# MODULIQ_UART.net
KiCad netlist of a schematic drawn in Altium Designer
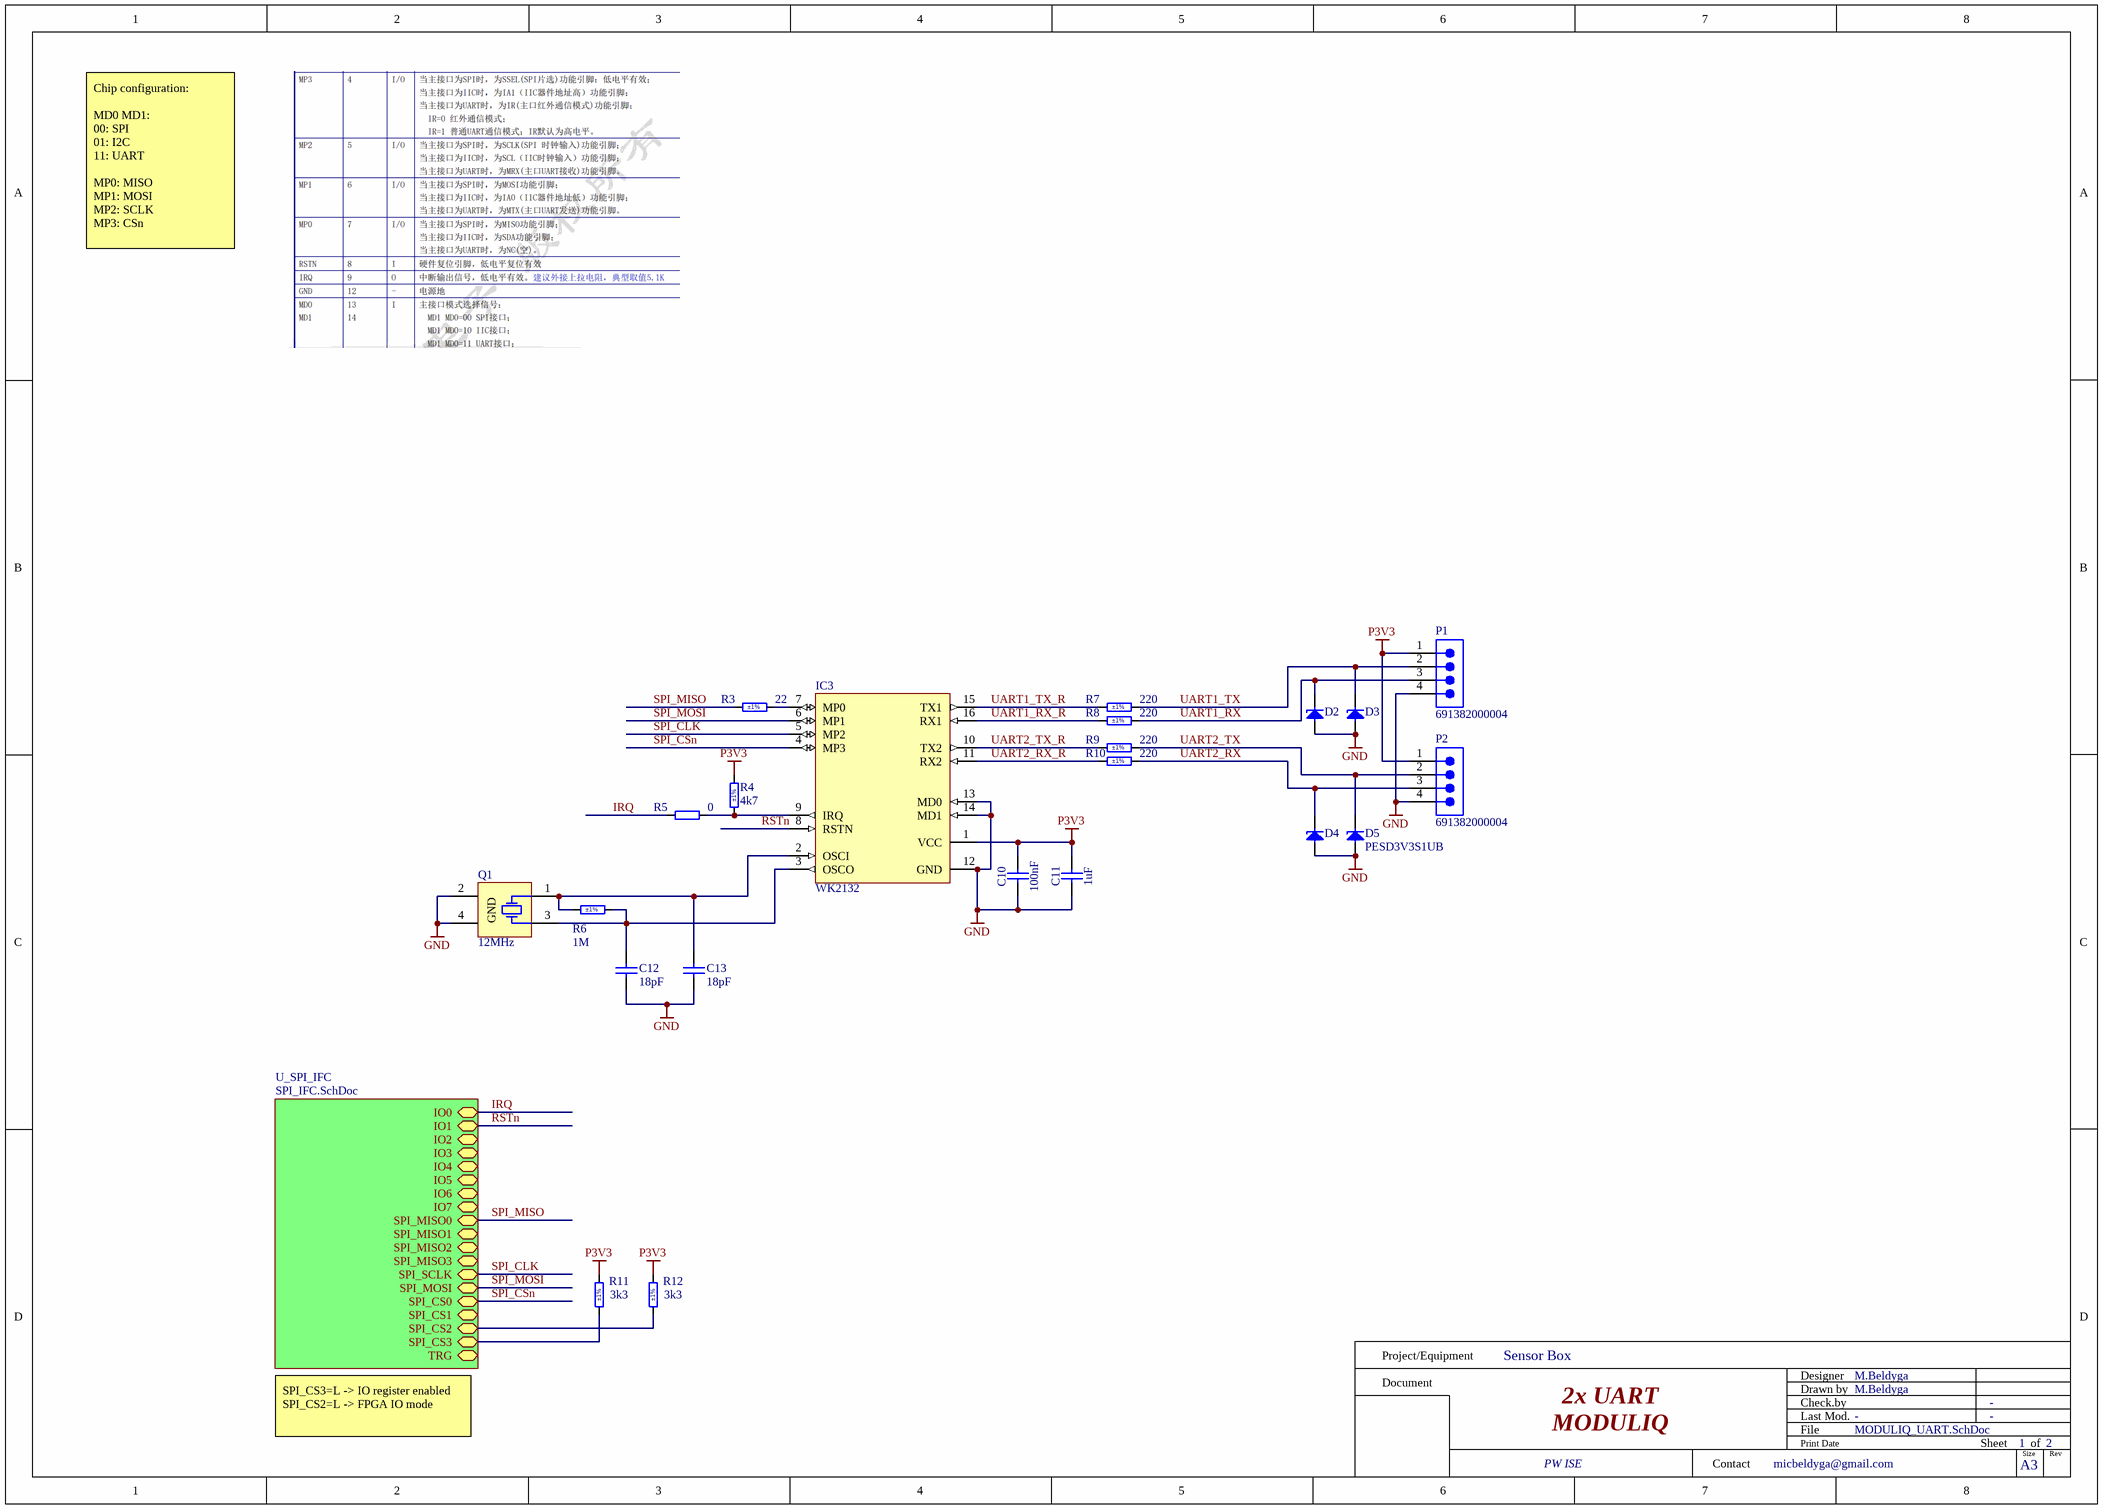
[diagram p0: MODULIQ_UART.SchDoc]

(export (version "E")
  (design (tool "Eeschema 10.0.6"))
  (components
    (comp (ref "C10")
      (value "100nF")
      (footprint "CAPC1005X55N")
      (description "Non-polarised capacitor")
      (fields
        (field (name "PART NUMBER") "CC0402_100NF_16V_10%_X7R")
        (field (name "VOLTAGE") "16V")
        (field (name "AUTHOR") "CERN DEM JLC")
      )
      (libsource (lib "Capacitors") (part "Capacitor - non polarized"))
    )
    (comp (ref "C11")
      (value "1uF")
      (footprint "CAPC1005X55N")
      (description "Non-polarised capacitor")
      (fields
        (field (name "PART NUMBER") "CC0402_1UF_16V_10%_X5R")
        (field (name "VOLTAGE") "16V")
        (field (name "AUTHOR") "CERN DEM JLC")
      )
      (libsource (lib "Capacitors") (part "Capacitor - non polarized"))
    )
    (comp (ref "C12")
      (value "18pF")
      (footprint "CAPC1005X55N")
      (description "Non-polarised capacitor")
      (fields
        (field (name "PART NUMBER") "CC0402_18PF_50V_5%_C0G")
        (field (name "VOLTAGE") "50V")
        (field (name "AUTHOR") "CERN DEM JLC")
      )
      (libsource (lib "Capacitors") (part "Capacitor - non polarized"))
    )
    (comp (ref "C13")
      (value "18pF")
      (footprint "CAPC1005X55N")
      (description "Non-polarised capacitor")
      (fields
        (field (name "PART NUMBER") "CC0402_18PF_50V_5%_C0G")
        (field (name "VOLTAGE") "50V")
        (field (name "AUTHOR") "CERN DEM JLC")
      )
      (libsource (lib "Capacitors") (part "Capacitor - non polarized"))
    )
    (comp (ref "D2")
      (value "PESD3V3S1UB")
      (footprint "SODFL1608X65N")
      (description "ESD protection diode")
      (fields
        (field (name "VOLTAGE") "3V3")
        (field (name "POWER") "330W")
        (field (name "AUTHOR") "CERN DEM JLC")
      )
      (libsource (lib "ICs And Semiconductors") (part "Diode ESD"))
    )
    (comp (ref "D3")
      (value "PESD3V3S1UB")
      (footprint "SODFL1608X65N")
      (description "ESD protection diode")
      (fields
        (field (name "VOLTAGE") "3V3")
        (field (name "POWER") "330W")
        (field (name "AUTHOR") "CERN DEM JLC")
      )
      (libsource (lib "ICs And Semiconductors") (part "Diode ESD"))
    )
    (comp (ref "D4")
      (value "PESD3V3S1UB")
      (footprint "SODFL1608X65N")
      (description "ESD protection diode")
      (fields
        (field (name "VOLTAGE") "3V3")
        (field (name "POWER") "330W")
        (field (name "AUTHOR") "CERN DEM JLC")
      )
      (libsource (lib "ICs And Semiconductors") (part "Diode ESD"))
    )
    (comp (ref "D5")
      (value "PESD3V3S1UB")
      (footprint "SODFL1608X65N")
      (description "ESD protection diode")
      (fields
        (field (name "VOLTAGE") "3V3")
        (field (name "POWER") "330W")
        (field (name "AUTHOR") "CERN DEM JLC")
      )
      (libsource (lib "ICs And Semiconductors") (part "Diode ESD"))
    )
    (comp (ref "IC3")
      (value "WK2132")
      (footprint "SOP65P780X195-16N")
      (description "2 Channel SPI-to-UART converter")
      (fields (field (name "MANUFACTURER PART NUMBER") "WK2132-ISSG") (field (name "MANUFACTURER") "Weikai"))
      (libsource (lib "mb") (part "WK2132"))
    )
    (comp (ref "P1")
      (value "691382000004")
      (footprint "691382000004")
      (description "WR-TBL Series 382 Vertical PCB Header, THT, pitch 2.5mm, 4p")
      (fields (field (name "MANUFACTURER") "Wurth Elektronik"))
      (libsource (lib "WE - Electromechanical Components") (part "TBL - 1R - 04P - Male"))
    )
    (comp (ref "P2")
      (value "691382000004")
      (footprint "691382000004")
      (description "WR-TBL Series 382 Vertical PCB Header, THT, pitch 2.5mm, 4p")
      (fields (field (name "MANUFACTURER") "Wurth Elektronik"))
      (libsource (lib "WE - Electromechanical Components") (part "TBL - 1R - 04P - Male"))
    )
    (comp (ref "Q1")
      (value "12MHz")
      (footprint "XTAL_TXC_7M")
      (description "Crystal 4 pins 1=XTAL Control 2=GND3=XTAL 4=GND")
      (fields
        (field (name "PART NUMBER") "XTAL_12MHZ_TXC_7M-12.000MAAJ-T")
        (field (name "MANUFACTURER") "TXC CORPORATION")
        (field (name "AUTHOR") "CERN DEM JLC")
      )
      (libsource (lib "ICs And Semiconductors") (part "Quartz Crystal 1X 2GND 3X 4GND"))
    )
    (comp (ref "R3")
      (value "22")
      (footprint "RESC1005X40N")
      (description "Resistor - 1%")
      (fields
        (field (name "TOLERANCE") "±1%")
        (field (name "PART NUMBER") "R0402_22R_1%_0.0625W_100PPM")
        (field (name "POWER") "0.0625W")
        (field (name "AUTHOR") "CERN DEM JLC")
      )
      (libsource (lib "Resistors") (part "Resistor - 1%"))
    )
    (comp (ref "R4")
      (value "4k7")
      (footprint "RESC1005X40N")
      (description "Resistor - 1%")
      (fields
        (field (name "TOLERANCE") "±1%")
        (field (name "PART NUMBER") "R0402_4K7_1%_0.0625W_100PPM")
        (field (name "POWER") "0.0625W")
        (field (name "AUTHOR") "CERN DEM JLC")
      )
      (libsource (lib "Resistors") (part "Resistor - 1%"))
    )
    (comp (ref "R5")
      (value "0")
      (footprint "RESC1005X40N")
      (description "Resistor")
      (fields
        (field (name "PART NUMBER") "R0402_0R_JUMPER")
        (field (name "MANUFACTURER") "GENERIC")
        (field (name "AUTHOR") "CERN DEM JLC")
      )
      (libsource (lib "Resistors") (part "Resistor"))
    )
    (comp (ref "R6")
      (value "1M")
      (footprint "RESC1005X40N")
      (description "Resistor - 1%")
      (fields
        (field (name "TOLERANCE") "±1%")
        (field (name "PART NUMBER") "R0402_1M_1%_0.0625W_100PPM")
        (field (name "POWER") "0.0625W")
        (field (name "AUTHOR") "CERN DEM JLC")
      )
      (libsource (lib "Resistors") (part "Resistor - 1%"))
    )
    (comp (ref "R7")
      (value "220")
      (footprint "RESC1608X55N")
      (description "Resistor - 1%")
      (fields
        (field (name "TOLERANCE") "±1%")
        (field (name "PART NUMBER") "R0603_220R_1%_0.1W_100PPM")
        (field (name "POWER") "0.1W")
        (field (name "AUTHOR") "CERN DEM JLC")
      )
      (libsource (lib "Resistors") (part "Resistor - 1%"))
    )
    (comp (ref "R8")
      (value "220")
      (footprint "RESC1608X55N")
      (description "Resistor - 1%")
      (fields
        (field (name "TOLERANCE") "±1%")
        (field (name "PART NUMBER") "R0603_220R_1%_0.1W_100PPM")
        (field (name "POWER") "0.1W")
        (field (name "AUTHOR") "CERN DEM JLC")
      )
      (libsource (lib "Resistors") (part "Resistor - 1%"))
    )
    (comp (ref "R9")
      (value "220")
      (footprint "RESC1608X55N")
      (description "Resistor - 1%")
      (fields
        (field (name "TOLERANCE") "±1%")
        (field (name "PART NUMBER") "R0603_220R_1%_0.1W_100PPM")
        (field (name "POWER") "0.1W")
        (field (name "AUTHOR") "CERN DEM JLC")
      )
      (libsource (lib "Resistors") (part "Resistor - 1%"))
    )
    (comp (ref "R10")
      (value "220")
      (footprint "RESC1608X55N")
      (description "Resistor - 1%")
      (fields
        (field (name "TOLERANCE") "±1%")
        (field (name "PART NUMBER") "R0603_220R_1%_0.1W_100PPM")
        (field (name "POWER") "0.1W")
        (field (name "AUTHOR") "CERN DEM JLC")
      )
      (libsource (lib "Resistors") (part "Resistor - 1%"))
    )
    (comp (ref "R11")
      (value "3k3")
      (footprint "RESC1005X40N")
      (description "Resistor - 1%")
      (fields
        (field (name "TOLERANCE") "±1%")
        (field (name "PART NUMBER") "R0402_3K3_1%_0.0625W_100PPM")
        (field (name "POWER") "0.0625W")
        (field (name "AUTHOR") "CERN DEM JLC")
      )
      (libsource (lib "Resistors") (part "Resistor - 1%"))
    )
    (comp (ref "R12")
      (value "3k3")
      (footprint "RESC1005X40N")
      (description "Resistor - 1%")
      (fields
        (field (name "TOLERANCE") "±1%")
        (field (name "PART NUMBER") "R0402_3K3_1%_0.0625W_100PPM")
        (field (name "POWER") "0.0625W")
        (field (name "AUTHOR") "CERN DEM JLC")
      )
      (libsource (lib "Resistors") (part "Resistor - 1%"))
    )
  )
  (nets
    (net (code "7") (name "/IRQ") (class "Default")
      (node (ref "R5") (pin "1") (pinfunction "1_1") (pintype "passive"))
    )
    (net (code "8") (name "/RSTn") (class "Default")
      (node (ref "IC3") (pin "8") (pinfunction "RSTN_8") (pintype "input"))
    )
    (net (code "9") (name "/SPI_CLK") (class "Default")
      (node (ref "IC3") (pin "5") (pinfunction "MP2_5") (pintype "bidirectional"))
    )
    (net (code "11") (name "/SPI_CS2") (class "Default")
      (node (ref "R12") (pin "2") (pinfunction "2_2") (pintype "passive"))
    )
    (net (code "12") (name "/SPI_CS3") (class "Default")
      (node (ref "R11") (pin "2") (pinfunction "2_2") (pintype "passive"))
    )
    (net (code "13") (name "/SPI_CSn") (class "Default")
      (node (ref "IC3") (pin "4") (pinfunction "MP3_4") (pintype "bidirectional"))
    )
    (net (code "14") (name "/SPI_MISO") (class "Default")
      (node (ref "R3") (pin "2") (pinfunction "2_2") (pintype "passive"))
    )
    (net (code "18") (name "/SPI_MOSI") (class "Default")
      (node (ref "IC3") (pin "6") (pinfunction "MP1_6") (pintype "bidirectional"))
    )
    (net (code "20") (name "/UART1_RX") (class "Default")
      (node (ref "D2") (pin "1") (pinfunction "C_1") (pintype "passive"))
      (node (ref "P1") (pin "3") (pinfunction "3_3") (pintype "passive"))
      (node (ref "R8") (pin "2") (pinfunction "2_2") (pintype "passive"))
    )
    (net (code "21") (name "/UART1_RX_R") (class "Default")
      (node (ref "IC3") (pin "16") (pinfunction "RX1_16") (pintype "input"))
      (node (ref "R8") (pin "1") (pinfunction "1_1") (pintype "passive"))
    )
    (net (code "22") (name "/UART1_TX") (class "Default")
      (node (ref "D3") (pin "1") (pinfunction "C_1") (pintype "passive"))
      (node (ref "P1") (pin "2") (pinfunction "2_2") (pintype "passive"))
      (node (ref "R7") (pin "2") (pinfunction "2_2") (pintype "passive"))
    )
    (net (code "23") (name "/UART1_TX_R") (class "Default")
      (node (ref "IC3") (pin "15") (pinfunction "TX1_15") (pintype "output"))
      (node (ref "R7") (pin "1") (pinfunction "1_1") (pintype "passive"))
    )
    (net (code "24") (name "/UART2_RX") (class "Default")
      (node (ref "D4") (pin "1") (pinfunction "C_1") (pintype "passive"))
      (node (ref "P2") (pin "3") (pinfunction "3_3") (pintype "passive"))
      (node (ref "R10") (pin "2") (pinfunction "2_2") (pintype "passive"))
    )
    (net (code "25") (name "/UART2_RX_R") (class "Default")
      (node (ref "IC3") (pin "11") (pinfunction "RX2_11") (pintype "input"))
      (node (ref "R10") (pin "1") (pinfunction "1_1") (pintype "passive"))
    )
    (net (code "26") (name "/UART2_TX") (class "Default")
      (node (ref "D5") (pin "1") (pinfunction "C_1") (pintype "passive"))
      (node (ref "P2") (pin "2") (pinfunction "2_2") (pintype "passive"))
      (node (ref "R9") (pin "2") (pinfunction "2_2") (pintype "passive"))
    )
    (net (code "27") (name "/UART2_TX_R") (class "Default")
      (node (ref "IC3") (pin "10") (pinfunction "TX2_10") (pintype "output"))
      (node (ref "R9") (pin "1") (pinfunction "1_1") (pintype "passive"))
    )
    (net (code "28") (name "GND") (class "Default")
      (node (ref "C10") (pin "1") (pinfunction "1_1") (pintype "passive"))
      (node (ref "C11") (pin "1") (pinfunction "1_1") (pintype "passive"))
      (node (ref "C12") (pin "1") (pinfunction "1_1") (pintype "passive"))
      (node (ref "C13") (pin "1") (pinfunction "1_1") (pintype "passive"))
      (node (ref "D2") (pin "2") (pinfunction "A_2") (pintype "passive"))
      (node (ref "D3") (pin "2") (pinfunction "A_2") (pintype "passive"))
      (node (ref "D4") (pin "2") (pinfunction "A_2") (pintype "passive"))
      (node (ref "D5") (pin "2") (pinfunction "A_2") (pintype "passive"))
      (node (ref "IC3") (pin "12") (pinfunction "GND_12") (pintype "power_in"))
      (node (ref "IC3") (pin "13") (pinfunction "MD0_13") (pintype "input"))
      (node (ref "IC3") (pin "14") (pinfunction "MD1_14") (pintype "input"))
      (node (ref "P1") (pin "4") (pinfunction "4_4") (pintype "passive"))
      (node (ref "P2") (pin "4") (pinfunction "4_4") (pintype "passive"))
      (node (ref "Q1") (pin "2") (pinfunction "GND_2") (pintype "power_in"))
      (node (ref "Q1") (pin "4") (pinfunction "GND_4") (pintype "power_in"))
    )
    (net (code "29") (name "Net-(IC3-IRQ)") (class "Default")
      (node (ref "IC3") (pin "9") (pinfunction "IRQ_9") (pintype "output"))
      (node (ref "R4") (pin "1") (pinfunction "1_1") (pintype "passive"))
      (node (ref "R5") (pin "2") (pinfunction "2_2") (pintype "passive"))
    )
    (net (code "30") (name "Net-(IC3-MP0)") (class "Default")
      (node (ref "IC3") (pin "7") (pinfunction "MP0_7") (pintype "bidirectional"))
      (node (ref "R3") (pin "1") (pinfunction "1_1") (pintype "passive"))
    )
    (net (code "31") (name "Net-(IC3-OSCI)") (class "Default")
      (node (ref "C13") (pin "2") (pinfunction "2_2") (pintype "passive"))
      (node (ref "IC3") (pin "2") (pinfunction "OSCI_2") (pintype "input"))
      (node (ref "Q1") (pin "1") (pinfunction "X_1") (pintype "passive"))
      (node (ref "R6") (pin "1") (pinfunction "1_1") (pintype "passive"))
    )
    (net (code "32") (name "Net-(IC3-OSCO)") (class "Default")
      (node (ref "C12") (pin "2") (pinfunction "2_2") (pintype "passive"))
      (node (ref "IC3") (pin "3") (pinfunction "OSCO_3") (pintype "output"))
      (node (ref "Q1") (pin "3") (pinfunction "X_3") (pintype "passive"))
      (node (ref "R6") (pin "2") (pinfunction "2_2") (pintype "passive"))
    )
    (net (code "33") (name "P3V3") (class "Default")
      (node (ref "C10") (pin "2") (pinfunction "2_2") (pintype "passive"))
      (node (ref "C11") (pin "2") (pinfunction "2_2") (pintype "passive"))
      (node (ref "IC3") (pin "1") (pinfunction "VCC_1") (pintype "power_in"))
      (node (ref "P1") (pin "1") (pinfunction "1_1") (pintype "passive"))
      (node (ref "P2") (pin "1") (pinfunction "1_1") (pintype "passive"))
      (node (ref "R11") (pin "1") (pinfunction "1_1") (pintype "passive"))
      (node (ref "R12") (pin "1") (pinfunction "1_1") (pintype "passive"))
      (node (ref "R4") (pin "2") (pinfunction "2_2") (pintype "passive"))
    )
  )
)
